# coil_driver.net
KiCad netlist of a schematic drawn in EAGLE
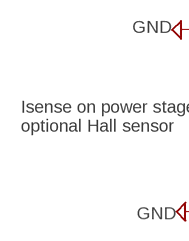
[diagram p0: schematic, sheet 1, part 1 of 2]
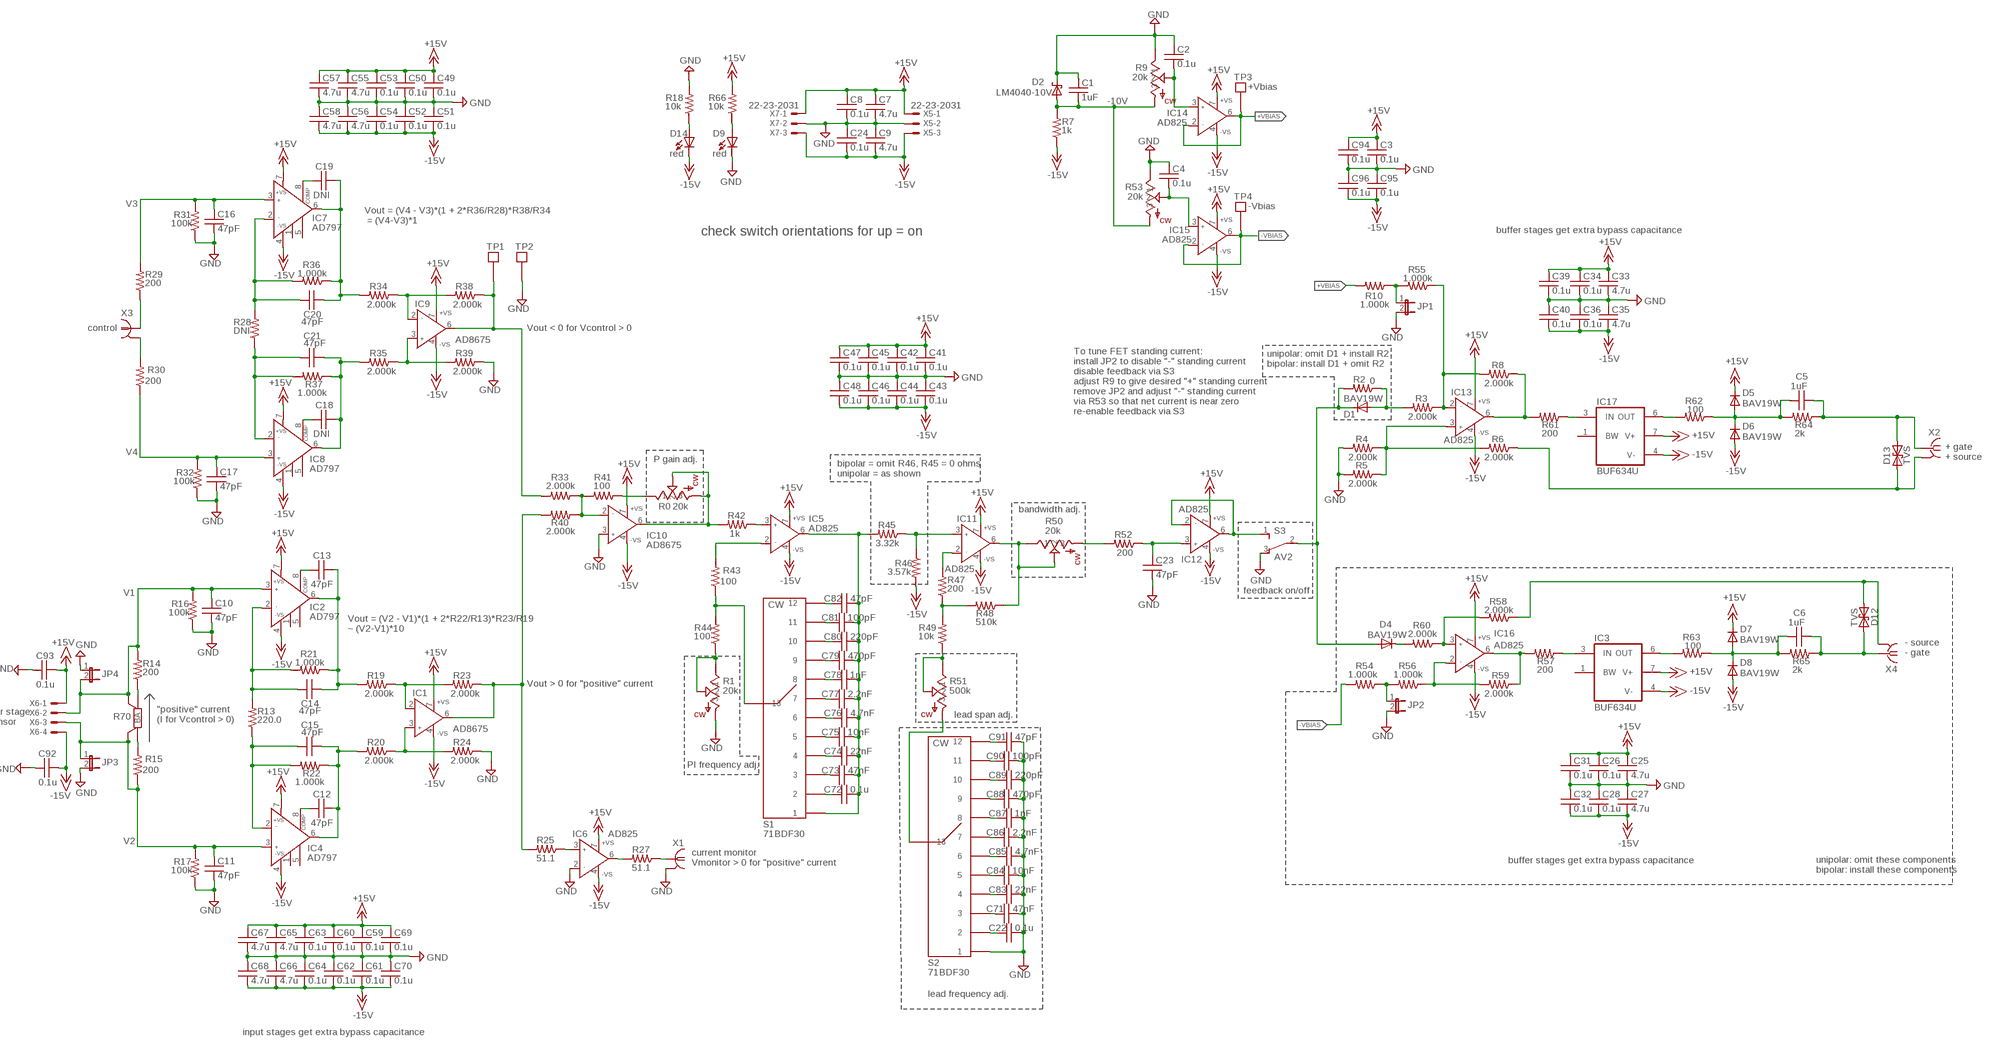
[diagram p1: schematic, sheet 1, part 2 of 2]

(export (version "E")
  (design (tool "Eeschema 10.0.6"))
  (components
    (comp (ref "C1")
      (value "1uF")
      (footprint "eagle-import:0603")
      (libsource (lib "eagle-import") (part "C0603"))
    )
    (comp (ref "C2")
      (value "0.1u")
      (footprint "eagle-import:0603")
      (libsource (lib "eagle-import") (part "C0603"))
    )
    (comp (ref "C3")
      (value "0.1u")
      (footprint "eagle-import:0603")
      (libsource (lib "eagle-import") (part "C0603"))
    )
    (comp (ref "C4")
      (value "0.1u")
      (footprint "eagle-import:0603")
      (libsource (lib "eagle-import") (part "C0603"))
    )
    (comp (ref "C5")
      (value "1uF")
      (footprint "eagle-import:0603")
      (libsource (lib "eagle-import") (part "C0603"))
    )
    (comp (ref "C6")
      (value "1uF")
      (footprint "eagle-import:0603")
      (libsource (lib "eagle-import") (part "C0603"))
    )
    (comp (ref "C7")
      (value "4.7u")
      (footprint "eagle-import:0603")
      (libsource (lib "eagle-import") (part "C0603"))
    )
    (comp (ref "C8")
      (value "0.1u")
      (footprint "eagle-import:0603")
      (libsource (lib "eagle-import") (part "C0603"))
    )
    (comp (ref "C9")
      (value "4.7u")
      (footprint "eagle-import:0603")
      (libsource (lib "eagle-import") (part "C0603"))
    )
    (comp (ref "C10")
      (value "47pF")
      (footprint "eagle-import:0603")
      (libsource (lib "eagle-import") (part "C0603"))
    )
    (comp (ref "C11")
      (value "47pF")
      (footprint "eagle-import:0603")
      (libsource (lib "eagle-import") (part "C0603"))
    )
    (comp (ref "C12")
      (value "47pF")
      (footprint "eagle-import:0603")
      (libsource (lib "eagle-import") (part "C0603"))
    )
    (comp (ref "C13")
      (value "47pF")
      (footprint "eagle-import:0603")
      (libsource (lib "eagle-import") (part "C0603"))
    )
    (comp (ref "C14")
      (value "47pF")
      (footprint "eagle-import:0603")
      (libsource (lib "eagle-import") (part "C0603"))
    )
    (comp (ref "C15")
      (value "47pF")
      (footprint "eagle-import:0603")
      (libsource (lib "eagle-import") (part "C0603"))
    )
    (comp (ref "C16")
      (value "47pF")
      (footprint "eagle-import:0603")
      (libsource (lib "eagle-import") (part "C0603"))
    )
    (comp (ref "C17")
      (value "47pF")
      (footprint "eagle-import:0603")
      (libsource (lib "eagle-import") (part "C0603"))
    )
    (comp (ref "C18")
      (value "DNI")
      (footprint "eagle-import:0603")
      (libsource (lib "eagle-import") (part "C0603"))
    )
    (comp (ref "C19")
      (value "DNI")
      (footprint "eagle-import:0603")
      (libsource (lib "eagle-import") (part "C0603"))
    )
    (comp (ref "C20")
      (value "47pF")
      (footprint "eagle-import:0603")
      (libsource (lib "eagle-import") (part "C0603"))
    )
    (comp (ref "C21")
      (value "47pF")
      (footprint "eagle-import:0603")
      (libsource (lib "eagle-import") (part "C0603"))
    )
    (comp (ref "C22")
      (value "0.1u")
      (footprint "eagle-import:0603")
      (libsource (lib "eagle-import") (part "C0603"))
    )
    (comp (ref "C23")
      (value "47pF")
      (footprint "eagle-import:0603")
      (libsource (lib "eagle-import") (part "C0603"))
    )
    (comp (ref "C24")
      (value "0.1u")
      (footprint "eagle-import:0603")
      (libsource (lib "eagle-import") (part "C0603"))
    )
    (comp (ref "C25")
      (value "4.7u")
      (footprint "eagle-import:0603")
      (libsource (lib "eagle-import") (part "C0603"))
    )
    (comp (ref "C26")
      (value "0.1u")
      (footprint "eagle-import:0603")
      (libsource (lib "eagle-import") (part "C0603"))
    )
    (comp (ref "C27")
      (value "4.7u")
      (footprint "eagle-import:0603")
      (libsource (lib "eagle-import") (part "C0603"))
    )
    (comp (ref "C28")
      (value "0.1u")
      (footprint "eagle-import:0603")
      (libsource (lib "eagle-import") (part "C0603"))
    )
    (comp (ref "C31")
      (value "0.1u")
      (footprint "eagle-import:0603")
      (libsource (lib "eagle-import") (part "C0603"))
    )
    (comp (ref "C32")
      (value "0.1u")
      (footprint "eagle-import:0603")
      (libsource (lib "eagle-import") (part "C0603"))
    )
    (comp (ref "C33")
      (value "4.7u")
      (footprint "eagle-import:0603")
      (libsource (lib "eagle-import") (part "C0603"))
    )
    (comp (ref "C34")
      (value "0.1u")
      (footprint "eagle-import:0603")
      (libsource (lib "eagle-import") (part "C0603"))
    )
    (comp (ref "C35")
      (value "4.7u")
      (footprint "eagle-import:0603")
      (libsource (lib "eagle-import") (part "C0603"))
    )
    (comp (ref "C36")
      (value "0.1u")
      (footprint "eagle-import:0603")
      (libsource (lib "eagle-import") (part "C0603"))
    )
    (comp (ref "C39")
      (value "0.1u")
      (footprint "eagle-import:0603")
      (libsource (lib "eagle-import") (part "C0603"))
    )
    (comp (ref "C40")
      (value "0.1u")
      (footprint "eagle-import:0603")
      (libsource (lib "eagle-import") (part "C0603"))
    )
    (comp (ref "C41")
      (value "0.1u")
      (footprint "eagle-import:0603")
      (libsource (lib "eagle-import") (part "C0603"))
    )
    (comp (ref "C42")
      (value "0.1u")
      (footprint "eagle-import:0603")
      (libsource (lib "eagle-import") (part "C0603"))
    )
    (comp (ref "C43")
      (value "0.1u")
      (footprint "eagle-import:0603")
      (libsource (lib "eagle-import") (part "C0603"))
    )
    (comp (ref "C44")
      (value "0.1u")
      (footprint "eagle-import:0603")
      (libsource (lib "eagle-import") (part "C0603"))
    )
    (comp (ref "C45")
      (value "0.1u")
      (footprint "eagle-import:0603")
      (libsource (lib "eagle-import") (part "C0603"))
    )
    (comp (ref "C46")
      (value "0.1u")
      (footprint "eagle-import:0603")
      (libsource (lib "eagle-import") (part "C0603"))
    )
    (comp (ref "C47")
      (value "0.1u")
      (footprint "eagle-import:0603")
      (libsource (lib "eagle-import") (part "C0603"))
    )
    (comp (ref "C48")
      (value "0.1u")
      (footprint "eagle-import:0603")
      (libsource (lib "eagle-import") (part "C0603"))
    )
    (comp (ref "C49")
      (value "0.1u")
      (footprint "eagle-import:0603")
      (libsource (lib "eagle-import") (part "C0603"))
    )
    (comp (ref "C50")
      (value "0.1u")
      (footprint "eagle-import:0603")
      (libsource (lib "eagle-import") (part "C0603"))
    )
    (comp (ref "C51")
      (value "0.1u")
      (footprint "eagle-import:0603")
      (libsource (lib "eagle-import") (part "C0603"))
    )
    (comp (ref "C52")
      (value "0.1u")
      (footprint "eagle-import:0603")
      (libsource (lib "eagle-import") (part "C0603"))
    )
    (comp (ref "C53")
      (value "0.1u")
      (footprint "eagle-import:0603")
      (libsource (lib "eagle-import") (part "C0603"))
    )
    (comp (ref "C54")
      (value "0.1u")
      (footprint "eagle-import:0603")
      (libsource (lib "eagle-import") (part "C0603"))
    )
    (comp (ref "C55")
      (value "4.7u")
      (footprint "eagle-import:0603")
      (libsource (lib "eagle-import") (part "C0603"))
    )
    (comp (ref "C56")
      (value "4.7u")
      (footprint "eagle-import:0603")
      (libsource (lib "eagle-import") (part "C0603"))
    )
    (comp (ref "C57")
      (value "4.7u")
      (footprint "eagle-import:0603")
      (libsource (lib "eagle-import") (part "C0603"))
    )
    (comp (ref "C58")
      (value "4.7u")
      (footprint "eagle-import:0603")
      (libsource (lib "eagle-import") (part "C0603"))
    )
    (comp (ref "C59")
      (value "0.1u")
      (footprint "eagle-import:0603")
      (libsource (lib "eagle-import") (part "C0603"))
    )
    (comp (ref "C60")
      (value "0.1u")
      (footprint "eagle-import:0603")
      (libsource (lib "eagle-import") (part "C0603"))
    )
    (comp (ref "C61")
      (value "0.1u")
      (footprint "eagle-import:0603")
      (libsource (lib "eagle-import") (part "C0603"))
    )
    (comp (ref "C62")
      (value "0.1u")
      (footprint "eagle-import:0603")
      (libsource (lib "eagle-import") (part "C0603"))
    )
    (comp (ref "C63")
      (value "0.1u")
      (footprint "eagle-import:0603")
      (libsource (lib "eagle-import") (part "C0603"))
    )
    (comp (ref "C64")
      (value "0.1u")
      (footprint "eagle-import:0603")
      (libsource (lib "eagle-import") (part "C0603"))
    )
    (comp (ref "C65")
      (value "4.7u")
      (footprint "eagle-import:0603")
      (libsource (lib "eagle-import") (part "C0603"))
    )
    (comp (ref "C66")
      (value "4.7u")
      (footprint "eagle-import:0603")
      (libsource (lib "eagle-import") (part "C0603"))
    )
    (comp (ref "C67")
      (value "4.7u")
      (footprint "eagle-import:0603")
      (libsource (lib "eagle-import") (part "C0603"))
    )
    (comp (ref "C68")
      (value "4.7u")
      (footprint "eagle-import:0603")
      (libsource (lib "eagle-import") (part "C0603"))
    )
    (comp (ref "C69")
      (value "0.1u")
      (footprint "eagle-import:0603")
      (libsource (lib "eagle-import") (part "C0603"))
    )
    (comp (ref "C70")
      (value "0.1u")
      (footprint "eagle-import:0603")
      (libsource (lib "eagle-import") (part "C0603"))
    )
    (comp (ref "C71")
      (value "47nF")
      (footprint "eagle-import:0603")
      (libsource (lib "eagle-import") (part "C0603"))
    )
    (comp (ref "C72")
      (value "0.1u")
      (footprint "eagle-import:0603")
      (libsource (lib "eagle-import") (part "C0603"))
    )
    (comp (ref "C73")
      (value "47nF")
      (footprint "eagle-import:0603")
      (libsource (lib "eagle-import") (part "C0603"))
    )
    (comp (ref "C74")
      (value "22nF")
      (footprint "eagle-import:0603")
      (libsource (lib "eagle-import") (part "C0603"))
    )
    (comp (ref "C75")
      (value "10nF")
      (footprint "eagle-import:0603")
      (libsource (lib "eagle-import") (part "C0603"))
    )
    (comp (ref "C76")
      (value "4.7nF")
      (footprint "eagle-import:0603")
      (libsource (lib "eagle-import") (part "C0603"))
    )
    (comp (ref "C77")
      (value "2.2nF")
      (footprint "eagle-import:0603")
      (libsource (lib "eagle-import") (part "C0603"))
    )
    (comp (ref "C78")
      (value "1nF")
      (footprint "eagle-import:0603")
      (libsource (lib "eagle-import") (part "C0603"))
    )
    (comp (ref "C79")
      (value "470pF")
      (footprint "eagle-import:0603")
      (libsource (lib "eagle-import") (part "C0603"))
    )
    (comp (ref "C80")
      (value "220pF")
      (footprint "eagle-import:0603")
      (libsource (lib "eagle-import") (part "C0603"))
    )
    (comp (ref "C81")
      (value "100pF")
      (footprint "eagle-import:0603")
      (libsource (lib "eagle-import") (part "C0603"))
    )
    (comp (ref "C82")
      (value "47pF")
      (footprint "eagle-import:0603")
      (libsource (lib "eagle-import") (part "C0603"))
    )
    (comp (ref "C83")
      (value "22nF")
      (footprint "eagle-import:0603")
      (libsource (lib "eagle-import") (part "C0603"))
    )
    (comp (ref "C84")
      (value "10nF")
      (footprint "eagle-import:0603")
      (libsource (lib "eagle-import") (part "C0603"))
    )
    (comp (ref "C85")
      (value "4.7nF")
      (footprint "eagle-import:0603")
      (libsource (lib "eagle-import") (part "C0603"))
    )
    (comp (ref "C86")
      (value "2.2nF")
      (footprint "eagle-import:0603")
      (libsource (lib "eagle-import") (part "C0603"))
    )
    (comp (ref "C87")
      (value "1nF")
      (footprint "eagle-import:0603")
      (libsource (lib "eagle-import") (part "C0603"))
    )
    (comp (ref "C88")
      (value "470pF")
      (footprint "eagle-import:0603")
      (libsource (lib "eagle-import") (part "C0603"))
    )
    (comp (ref "C89")
      (value "220pF")
      (footprint "eagle-import:0603")
      (libsource (lib "eagle-import") (part "C0603"))
    )
    (comp (ref "C90")
      (value "100pF")
      (footprint "eagle-import:0603")
      (libsource (lib "eagle-import") (part "C0603"))
    )
    (comp (ref "C91")
      (value "47pF")
      (footprint "eagle-import:0603")
      (libsource (lib "eagle-import") (part "C0603"))
    )
    (comp (ref "C92")
      (value "0.1u")
      (footprint "eagle-import:0603")
      (libsource (lib "eagle-import") (part "C0603"))
    )
    (comp (ref "C93")
      (value "0.1u")
      (footprint "eagle-import:0603")
      (libsource (lib "eagle-import") (part "C0603"))
    )
    (comp (ref "C94")
      (value "0.1u")
      (footprint "eagle-import:0603")
      (libsource (lib "eagle-import") (part "C0603"))
    )
    (comp (ref "C95")
      (value "0.1u")
      (footprint "eagle-import:0603")
      (libsource (lib "eagle-import") (part "C0603"))
    )
    (comp (ref "C96")
      (value "0.1u")
      (footprint "eagle-import:0603")
      (libsource (lib "eagle-import") (part "C0603"))
    )
    (comp (ref "D1")
      (value "BAV19W")
      (footprint "eagle-import:SOD123")
      (libsource (lib "eagle-import") (part "DIODE-SOD123"))
    )
    (comp (ref "D2")
      (value "LM4040-10V")
      (footprint "eagle-import:SOT23")
      (libsource (lib "eagle-import") (part "LM4040"))
    )
    (comp (ref "D4")
      (value "BAV19W")
      (footprint "eagle-import:SOD123")
      (libsource (lib "eagle-import") (part "DIODE-SOD123"))
    )
    (comp (ref "D5")
      (value "BAV19W")
      (footprint "eagle-import:SOD123")
      (libsource (lib "eagle-import") (part "DIODE-SOD123"))
    )
    (comp (ref "D6")
      (value "BAV19W")
      (footprint "eagle-import:SOD123")
      (libsource (lib "eagle-import") (part "DIODE-SOD123"))
    )
    (comp (ref "D7")
      (value "BAV19W")
      (footprint "eagle-import:SOD123")
      (libsource (lib "eagle-import") (part "DIODE-SOD123"))
    )
    (comp (ref "D8")
      (value "BAV19W")
      (footprint "eagle-import:SOD123")
      (libsource (lib "eagle-import") (part "DIODE-SOD123"))
    )
    (comp (ref "D9")
      (value "red")
      (footprint "eagle-import:LED0603")
      (libsource (lib "eagle-import") (part "LED0603"))
    )
    (comp (ref "D12")
      (value "TVS")
      (footprint "eagle-import:SMA-DIODE")
      (libsource (lib "eagle-import") (part "TVS"))
    )
    (comp (ref "D13")
      (value "TVS")
      (footprint "eagle-import:SMA-DIODE")
      (libsource (lib "eagle-import") (part "TVS"))
    )
    (comp (ref "D14")
      (value "red")
      (footprint "eagle-import:LED0603")
      (libsource (lib "eagle-import") (part "LED0603"))
    )
    (comp (ref "IC1")
      (value "AD8675")
      (footprint "eagle-import:SO8")
      (fields (field (name "MF") "ALTERA CORPORATION") (field (name "MPN") "AD825ARZ"))
      (libsource (lib "eagle-import") (part "AD825_BR"))
    )
    (comp (ref "IC2")
      (value "AD797")
      (footprint "eagle-import:SO8")
      (fields (field (name "MF") "ALTERA CORPORATION") (field (name "MPN") "AD797ARZ"))
      (libsource (lib "eagle-import") (part "AD797_AR"))
    )
    (comp (ref "IC3")
      (value "BUF634U")
      (footprint "eagle-import:SO08")
      (fields (field (name "MF") "TEXAS INSTRUMENTS"))
      (libsource (lib "eagle-import") (part "BUF634U"))
    )
    (comp (ref "IC4")
      (value "AD797")
      (footprint "eagle-import:SO8")
      (fields (field (name "MF") "ALTERA CORPORATION") (field (name "MPN") "AD797ARZ"))
      (libsource (lib "eagle-import") (part "AD797_BR"))
    )
    (comp (ref "IC5")
      (value "AD825")
      (footprint "eagle-import:SO08")
      (libsource (lib "eagle-import") (part "AD825_A"))
    )
    (comp (ref "IC6")
      (value "AD825")
      (footprint "eagle-import:SO08")
      (libsource (lib "eagle-import") (part "AD825_A"))
    )
    (comp (ref "IC7")
      (value "AD797")
      (footprint "eagle-import:SO8")
      (fields (field (name "MF") "ALTERA CORPORATION") (field (name "MPN") "AD797ARZ"))
      (libsource (lib "eagle-import") (part "AD797_AR"))
    )
    (comp (ref "IC8")
      (value "AD797")
      (footprint "eagle-import:SO8")
      (fields (field (name "MF") "ALTERA CORPORATION") (field (name "MPN") "AD797ARZ"))
      (libsource (lib "eagle-import") (part "AD797_BR"))
    )
    (comp (ref "IC9")
      (value "AD8675")
      (footprint "eagle-import:SO8")
      (fields (field (name "MF") "ALTERA CORPORATION") (field (name "MPN") "AD825ARZ"))
      (libsource (lib "eagle-import") (part "AD825_BR"))
    )
    (comp (ref "IC10")
      (value "AD8675")
      (footprint "eagle-import:SO8")
      (fields (field (name "MF") "ALTERA CORPORATION") (field (name "MPN") "AD825ARZ"))
      (libsource (lib "eagle-import") (part "AD825_BR"))
    )
    (comp (ref "IC11")
      (value "AD825")
      (footprint "eagle-import:SO08")
      (libsource (lib "eagle-import") (part "AD825_A"))
    )
    (comp (ref "IC12")
      (value "AD825")
      (footprint "eagle-import:SO8")
      (fields (field (name "MF") "ALTERA CORPORATION") (field (name "MPN") "AD825ARZ"))
      (libsource (lib "eagle-import") (part "AD825_BR"))
    )
    (comp (ref "IC13")
      (value "AD825")
      (footprint "eagle-import:SO8")
      (fields (field (name "MF") "ALTERA CORPORATION") (field (name "MPN") "AD825ARZ"))
      (libsource (lib "eagle-import") (part "AD825_BR"))
    )
    (comp (ref "IC14")
      (value "AD825")
      (footprint "eagle-import:SO08")
      (libsource (lib "eagle-import") (part "AD825_A"))
    )
    (comp (ref "IC15")
      (value "AD825")
      (footprint "eagle-import:SO08")
      (libsource (lib "eagle-import") (part "AD825_A"))
    )
    (comp (ref "IC16")
      (value "AD825")
      (footprint "eagle-import:SO08")
      (libsource (lib "eagle-import") (part "AD825_A"))
    )
    (comp (ref "IC17")
      (value "BUF634U")
      (footprint "eagle-import:SO08")
      (fields (field (name "MF") "TEXAS INSTRUMENTS"))
      (libsource (lib "eagle-import") (part "BUF634U"))
    )
    (comp (ref "JP1")
      (value "JP1E")
      (footprint "eagle-import:JP1")
      (libsource (lib "eagle-import") (part "JP1E"))
    )
    (comp (ref "JP2")
      (value "JP1E")
      (footprint "eagle-import:JP1")
      (libsource (lib "eagle-import") (part "JP1E"))
    )
    (comp (ref "JP3")
      (value "JP1E")
      (footprint "eagle-import:JP1")
      (libsource (lib "eagle-import") (part "JP1E"))
    )
    (comp (ref "JP4")
      (value "JP1E")
      (footprint "eagle-import:JP1")
      (libsource (lib "eagle-import") (part "JP1E"))
    )
    (comp (ref "R0")
      (value "20k")
      (footprint "eagle-import:3590")
      (libsource (lib "eagle-import") (part "POT"))
    )
    (comp (ref "R1")
      (value "20k")
      (footprint "eagle-import:SP19L")
      (libsource (lib "eagle-import") (part "TRIM_US-B90P"))
    )
    (comp (ref "R2")
      (value "0")
      (footprint "eagle-import:0603")
      (libsource (lib "eagle-import") (part "R0603"))
    )
    (comp (ref "R3")
      (value "2.000k")
      (footprint "eagle-import:0603")
      (libsource (lib "eagle-import") (part "R0603"))
    )
    (comp (ref "R4")
      (value "2.000k")
      (footprint "eagle-import:0603")
      (libsource (lib "eagle-import") (part "R0603"))
    )
    (comp (ref "R5")
      (value "2.000k")
      (footprint "eagle-import:0603")
      (libsource (lib "eagle-import") (part "R0603"))
    )
    (comp (ref "R6")
      (value "2.000k")
      (footprint "eagle-import:0603")
      (libsource (lib "eagle-import") (part "R0603"))
    )
    (comp (ref "R7")
      (value "1k")
      (footprint "eagle-import:0603")
      (libsource (lib "eagle-import") (part "R0603"))
    )
    (comp (ref "R8")
      (value "2.000k")
      (footprint "eagle-import:0603")
      (libsource (lib "eagle-import") (part "R0603"))
    )
    (comp (ref "R9")
      (value "20k")
      (footprint "eagle-import:SP19L")
      (libsource (lib "eagle-import") (part "TRIM_US-B90P"))
    )
    (comp (ref "R10")
      (value "1.000k")
      (footprint "eagle-import:0603")
      (libsource (lib "eagle-import") (part "R0603"))
    )
    (comp (ref "R13")
      (value "220.0")
      (footprint "eagle-import:0603")
      (libsource (lib "eagle-import") (part "R0603"))
    )
    (comp (ref "R14")
      (value "200")
      (footprint "eagle-import:0603")
      (libsource (lib "eagle-import") (part "R0603"))
    )
    (comp (ref "R15")
      (value "200")
      (footprint "eagle-import:0603")
      (libsource (lib "eagle-import") (part "R0603"))
    )
    (comp (ref "R16")
      (value "100k")
      (footprint "eagle-import:0603")
      (libsource (lib "eagle-import") (part "R0603"))
    )
    (comp (ref "R17")
      (value "100k")
      (footprint "eagle-import:0603")
      (libsource (lib "eagle-import") (part "R0603"))
    )
    (comp (ref "R18")
      (value "10k")
      (footprint "eagle-import:0603")
      (libsource (lib "eagle-import") (part "R0603"))
    )
    (comp (ref "R19")
      (value "2.000k")
      (footprint "eagle-import:0603")
      (libsource (lib "eagle-import") (part "R0603"))
    )
    (comp (ref "R20")
      (value "2.000k")
      (footprint "eagle-import:0603")
      (libsource (lib "eagle-import") (part "R0603"))
    )
    (comp (ref "R21")
      (value "1.000k")
      (footprint "eagle-import:0603")
      (libsource (lib "eagle-import") (part "R0603"))
    )
    (comp (ref "R22")
      (value "1.000k")
      (footprint "eagle-import:0603")
      (libsource (lib "eagle-import") (part "R0603"))
    )
    (comp (ref "R23")
      (value "2.000k")
      (footprint "eagle-import:0603")
      (libsource (lib "eagle-import") (part "R0603"))
    )
    (comp (ref "R24")
      (value "2.000k")
      (footprint "eagle-import:0603")
      (libsource (lib "eagle-import") (part "R0603"))
    )
    (comp (ref "R25")
      (value "51.1")
      (footprint "eagle-import:0603")
      (libsource (lib "eagle-import") (part "R0603"))
    )
    (comp (ref "R27")
      (value "51.1")
      (footprint "eagle-import:0603")
      (libsource (lib "eagle-import") (part "R0603"))
    )
    (comp (ref "R28")
      (value "DNI")
      (footprint "eagle-import:0603")
      (libsource (lib "eagle-import") (part "R0603"))
    )
    (comp (ref "R29")
      (value "200")
      (footprint "eagle-import:0603")
      (libsource (lib "eagle-import") (part "R0603"))
    )
    (comp (ref "R30")
      (value "200")
      (footprint "eagle-import:0603")
      (libsource (lib "eagle-import") (part "R0603"))
    )
    (comp (ref "R31")
      (value "100k")
      (footprint "eagle-import:0603")
      (libsource (lib "eagle-import") (part "R0603"))
    )
    (comp (ref "R32")
      (value "100k")
      (footprint "eagle-import:0603")
      (libsource (lib "eagle-import") (part "R0603"))
    )
    (comp (ref "R33")
      (value "2.000k")
      (footprint "eagle-import:0603")
      (libsource (lib "eagle-import") (part "R0603"))
    )
    (comp (ref "R34")
      (value "2.000k")
      (footprint "eagle-import:0603")
      (libsource (lib "eagle-import") (part "R0603"))
    )
    (comp (ref "R35")
      (value "2.000k")
      (footprint "eagle-import:0603")
      (libsource (lib "eagle-import") (part "R0603"))
    )
    (comp (ref "R36")
      (value "1.000k")
      (footprint "eagle-import:0603")
      (libsource (lib "eagle-import") (part "R0603"))
    )
    (comp (ref "R37")
      (value "1.000k")
      (footprint "eagle-import:0603")
      (libsource (lib "eagle-import") (part "R0603"))
    )
    (comp (ref "R38")
      (value "2.000k")
      (footprint "eagle-import:0603")
      (libsource (lib "eagle-import") (part "R0603"))
    )
    (comp (ref "R39")
      (value "2.000k")
      (footprint "eagle-import:0603")
      (libsource (lib "eagle-import") (part "R0603"))
    )
    (comp (ref "R40")
      (value "2.000k")
      (footprint "eagle-import:0603")
      (libsource (lib "eagle-import") (part "R0603"))
    )
    (comp (ref "R41")
      (value "100")
      (footprint "eagle-import:0603")
      (libsource (lib "eagle-import") (part "R0603"))
    )
    (comp (ref "R42")
      (value "1k")
      (footprint "eagle-import:0603")
      (libsource (lib "eagle-import") (part "R0603"))
    )
    (comp (ref "R43")
      (value "100")
      (footprint "eagle-import:0603")
      (libsource (lib "eagle-import") (part "R0603"))
    )
    (comp (ref "R44")
      (value "100")
      (footprint "eagle-import:0603")
      (libsource (lib "eagle-import") (part "R0603"))
    )
    (comp (ref "R45")
      (value "3.32k")
      (footprint "eagle-import:0603")
      (libsource (lib "eagle-import") (part "R0603"))
    )
    (comp (ref "R46")
      (value "3.57k")
      (footprint "eagle-import:0603")
      (libsource (lib "eagle-import") (part "R0603"))
    )
    (comp (ref "R47")
      (value "200")
      (footprint "eagle-import:0603")
      (libsource (lib "eagle-import") (part "R0603"))
    )
    (comp (ref "R48")
      (value "510k")
      (footprint "eagle-import:0603")
      (libsource (lib "eagle-import") (part "R0603"))
    )
    (comp (ref "R49")
      (value "10k")
      (footprint "eagle-import:0603")
      (libsource (lib "eagle-import") (part "R0603"))
    )
    (comp (ref "R50")
      (value "20k")
      (footprint "eagle-import:SP19L")
      (libsource (lib "eagle-import") (part "TRIM_US-B90P"))
    )
    (comp (ref "R51")
      (value "500k")
      (footprint "eagle-import:SP19L")
      (libsource (lib "eagle-import") (part "TRIM_US-B90P"))
    )
    (comp (ref "R52")
      (value "200")
      (footprint "eagle-import:0603")
      (libsource (lib "eagle-import") (part "R0603"))
    )
    (comp (ref "R53")
      (value "20k")
      (footprint "eagle-import:SP19L")
      (libsource (lib "eagle-import") (part "TRIM_US-B90P"))
    )
    (comp (ref "R54")
      (value "1.000k")
      (footprint "eagle-import:0603")
      (libsource (lib "eagle-import") (part "R0603"))
    )
    (comp (ref "R55")
      (value "1.000k")
      (footprint "eagle-import:0603")
      (libsource (lib "eagle-import") (part "R0603"))
    )
    (comp (ref "R56")
      (value "1.000k")
      (footprint "eagle-import:0603")
      (libsource (lib "eagle-import") (part "R0603"))
    )
    (comp (ref "R57")
      (value "200")
      (footprint "eagle-import:0603")
      (libsource (lib "eagle-import") (part "R0603"))
    )
    (comp (ref "R58")
      (value "2.000k")
      (footprint "eagle-import:0603")
      (libsource (lib "eagle-import") (part "R0603"))
    )
    (comp (ref "R59")
      (value "2.000k")
      (footprint "eagle-import:0603")
      (libsource (lib "eagle-import") (part "R0603"))
    )
    (comp (ref "R60")
      (value "2.000k")
      (footprint "eagle-import:0603")
      (libsource (lib "eagle-import") (part "R0603"))
    )
    (comp (ref "R61")
      (value "200")
      (footprint "eagle-import:0603")
      (libsource (lib "eagle-import") (part "R0603"))
    )
    (comp (ref "R62")
      (value "100")
      (footprint "eagle-import:0603")
      (libsource (lib "eagle-import") (part "R0603"))
    )
    (comp (ref "R63")
      (value "100")
      (footprint "eagle-import:0603")
      (libsource (lib "eagle-import") (part "R0603"))
    )
    (comp (ref "R64")
      (value "2k")
      (footprint "eagle-import:0603")
      (libsource (lib "eagle-import") (part "R0603"))
    )
    (comp (ref "R65")
      (value "2k")
      (footprint "eagle-import:0603")
      (libsource (lib "eagle-import") (part "R0603"))
    )
    (comp (ref "R66")
      (value "10k")
      (footprint "eagle-import:0603")
      (libsource (lib "eagle-import") (part "R0603"))
    )
    (comp (ref "R70")
      (value "RSENSE")
      (footprint "eagle-import:22-23-2041")
      (libsource (lib "eagle-import") (part "RSENSE"))
    )
    (comp (ref "S1")
      (value "71BDF30")
      (footprint "eagle-import:71BDF")
      (libsource (lib "eagle-import") (part "71BDF30"))
    )
    (comp (ref "S2")
      (value "71BDF30")
      (footprint "eagle-import:71BDF")
      (libsource (lib "eagle-import") (part "71BDF30"))
    )
    (comp (ref "S3")
      (value "AV2")
      (footprint "eagle-import:SPDT-AV2")
      (libsource (lib "eagle-import") (part "SPDT"))
    )
    (comp (ref "TP1")
      (value "TESTPOINT")
      (footprint "eagle-import:TESTPOINT")
      (libsource (lib "eagle-import") (part "TESTPOINT"))
    )
    (comp (ref "TP2")
      (value "TESTPOINT")
      (footprint "eagle-import:TESTPOINT")
      (libsource (lib "eagle-import") (part "TESTPOINT"))
    )
    (comp (ref "TP3")
      (value "TESTPOINT")
      (footprint "eagle-import:TESTPOINT")
      (libsource (lib "eagle-import") (part "TESTPOINT"))
    )
    (comp (ref "TP4")
      (value "TESTPOINT")
      (footprint "eagle-import:TESTPOINT")
      (libsource (lib "eagle-import") (part "TESTPOINT"))
    )
    (comp (ref "X1")
      (value "1-227161-0")
      (footprint "eagle-import:AMP_227161")
      (fields (field (name "MF") "TYCO ELECTRONICS") (field (name "MPN") "1-227161"))
      (libsource (lib "eagle-import") (part "?2271611--0"))
    )
    (comp (ref "X2")
      (value "BU-SMA-H")
      (footprint "eagle-import:BU-SMA-H")
      (libsource (lib "eagle-import") (part "BU-SMA-H"))
    )
    (comp (ref "X3")
      (value "1-227161-0")
      (footprint "eagle-import:AMP_227161")
      (fields (field (name "MF") "TYCO ELECTRONICS") (field (name "MPN") "1-227161"))
      (libsource (lib "eagle-import") (part "?2271611--0"))
    )
    (comp (ref "X4")
      (value "BU-SMA-H")
      (footprint "eagle-import:BU-SMA-H")
      (libsource (lib "eagle-import") (part "BU-SMA-H"))
    )
    (comp (ref "X5")
      (value "22-23-2031")
      (footprint "eagle-import:22-23-2031")
      (fields (field (name "MF") "MOLEX"))
      (libsource (lib "eagle-import") (part "22-23-2031"))
    )
    (comp (ref "X6")
      (value "22-23-2041")
      (footprint "eagle-import:22-23-2041")
      (fields (field (name "MF") "MOLEX"))
      (libsource (lib "eagle-import") (part "22-23-2041"))
    )
    (comp (ref "X7")
      (value "22-23-2031")
      (footprint "eagle-import:22-23-2031")
      (fields (field (name "MF") "MOLEX"))
      (libsource (lib "eagle-import") (part "22-23-2031"))
    )
  )
  (nets
    (net (code "1") (name "+15V") (class "Default")
      (node (ref "C25") (pin "1") (pinfunction "1_1") (pintype "passive"))
      (node (ref "C26") (pin "1") (pinfunction "1_1") (pintype "passive"))
      (node (ref "C3") (pin "1") (pinfunction "1_1") (pintype "passive"))
      (node (ref "C31") (pin "1") (pinfunction "1_1") (pintype "passive"))
      (node (ref "C33") (pin "1") (pinfunction "1_1") (pintype "passive"))
      (node (ref "C34") (pin "1") (pinfunction "1_1") (pintype "passive"))
      (node (ref "C39") (pin "1") (pinfunction "1_1") (pintype "passive"))
      (node (ref "C41") (pin "1") (pinfunction "1_1") (pintype "passive"))
      (node (ref "C42") (pin "1") (pinfunction "1_1") (pintype "passive"))
      (node (ref "C45") (pin "1") (pinfunction "1_1") (pintype "passive"))
      (node (ref "C47") (pin "1") (pinfunction "1_1") (pintype "passive"))
      (node (ref "C49") (pin "1") (pinfunction "1_1") (pintype "passive"))
      (node (ref "C50") (pin "1") (pinfunction "1_1") (pintype "passive"))
      (node (ref "C53") (pin "1") (pinfunction "1_1") (pintype "passive"))
      (node (ref "C55") (pin "1") (pinfunction "1_1") (pintype "passive"))
      (node (ref "C57") (pin "1") (pinfunction "1_1") (pintype "passive"))
      (node (ref "C59") (pin "1") (pinfunction "1_1") (pintype "passive"))
      (node (ref "C60") (pin "1") (pinfunction "1_1") (pintype "passive"))
      (node (ref "C63") (pin "1") (pinfunction "1_1") (pintype "passive"))
      (node (ref "C65") (pin "1") (pinfunction "1_1") (pintype "passive"))
      (node (ref "C67") (pin "1") (pinfunction "1_1") (pintype "passive"))
      (node (ref "C69") (pin "1") (pinfunction "1_1") (pintype "passive"))
      (node (ref "C7") (pin "1") (pinfunction "1_1") (pintype "passive"))
      (node (ref "C8") (pin "1") (pinfunction "1_1") (pintype "passive"))
      (node (ref "C93") (pin "2") (pinfunction "2_2") (pintype "passive"))
      (node (ref "C94") (pin "1") (pinfunction "1_1") (pintype "passive"))
      (node (ref "D5") (pin "C") (pinfunction "C_C") (pintype "passive"))
      (node (ref "D7") (pin "C") (pinfunction "C_C") (pintype "passive"))
      (node (ref "IC1") (pin "7") (pinfunction "+VS_7") (pintype "input"))
      (node (ref "IC10") (pin "7") (pinfunction "+VS_7") (pintype "input"))
      (node (ref "IC11") (pin "7") (pinfunction "+VS_7") (pintype "input"))
      (node (ref "IC12") (pin "7") (pinfunction "+VS_7") (pintype "input"))
      (node (ref "IC13") (pin "7") (pinfunction "+VS_7") (pintype "input"))
      (node (ref "IC14") (pin "7") (pinfunction "+VS_7") (pintype "input"))
      (node (ref "IC15") (pin "7") (pinfunction "+VS_7") (pintype "input"))
      (node (ref "IC16") (pin "7") (pinfunction "+VS_7") (pintype "input"))
      (node (ref "IC17") (pin "7") (pinfunction "V+_7") (pintype "power_in"))
      (node (ref "IC2") (pin "7") (pinfunction "+VS_7") (pintype "input"))
      (node (ref "IC3") (pin "7") (pinfunction "V+_7") (pintype "power_in"))
      (node (ref "IC4") (pin "7") (pinfunction "+VS_7") (pintype "input"))
      (node (ref "IC5") (pin "7") (pinfunction "+VS_7") (pintype "input"))
      (node (ref "IC6") (pin "7") (pinfunction "+VS_7") (pintype "input"))
      (node (ref "IC7") (pin "7") (pinfunction "+VS_7") (pintype "input"))
      (node (ref "IC8") (pin "7") (pinfunction "+VS_7") (pintype "input"))
      (node (ref "IC9") (pin "7") (pinfunction "+VS_7") (pintype "input"))
      (node (ref "R66") (pin "2") (pinfunction "2_2") (pintype "passive"))
      (node (ref "X5") (pin "1") (pinfunction "S_1") (pintype "passive"))
      (node (ref "X6") (pin "1") (pinfunction "S_1") (pintype "passive"))
      (node (ref "X7") (pin "1") (pinfunction "S_1") (pintype "passive"))
    )
    (net (code "2") (name "+VBIAS") (class "Default")
      (node (ref "IC14") (pin "2") (pinfunction "IN-_2") (pintype "input"))
      (node (ref "IC14") (pin "6") (pinfunction "OUT_6") (pintype "output"))
      (node (ref "R10") (pin "2") (pinfunction "2_2") (pintype "passive"))
      (node (ref "TP3") (pin "P$1") (pinfunction "P$1_P$1") (pintype "bidirectional"))
    )
    (net (code "3") (name "-15V") (class "Default")
      (node (ref "C24") (pin "2") (pinfunction "2_2") (pintype "passive"))
      (node (ref "C27") (pin "2") (pinfunction "2_2") (pintype "passive"))
      (node (ref "C28") (pin "2") (pinfunction "2_2") (pintype "passive"))
      (node (ref "C32") (pin "2") (pinfunction "2_2") (pintype "passive"))
      (node (ref "C35") (pin "2") (pinfunction "2_2") (pintype "passive"))
      (node (ref "C36") (pin "2") (pinfunction "2_2") (pintype "passive"))
      (node (ref "C40") (pin "2") (pinfunction "2_2") (pintype "passive"))
      (node (ref "C43") (pin "2") (pinfunction "2_2") (pintype "passive"))
      (node (ref "C44") (pin "2") (pinfunction "2_2") (pintype "passive"))
      (node (ref "C46") (pin "2") (pinfunction "2_2") (pintype "passive"))
      (node (ref "C48") (pin "2") (pinfunction "2_2") (pintype "passive"))
      (node (ref "C51") (pin "2") (pinfunction "2_2") (pintype "passive"))
      (node (ref "C52") (pin "2") (pinfunction "2_2") (pintype "passive"))
      (node (ref "C54") (pin "2") (pinfunction "2_2") (pintype "passive"))
      (node (ref "C56") (pin "2") (pinfunction "2_2") (pintype "passive"))
      (node (ref "C58") (pin "2") (pinfunction "2_2") (pintype "passive"))
      (node (ref "C61") (pin "2") (pinfunction "2_2") (pintype "passive"))
      (node (ref "C62") (pin "2") (pinfunction "2_2") (pintype "passive"))
      (node (ref "C64") (pin "2") (pinfunction "2_2") (pintype "passive"))
      (node (ref "C66") (pin "2") (pinfunction "2_2") (pintype "passive"))
      (node (ref "C68") (pin "2") (pinfunction "2_2") (pintype "passive"))
      (node (ref "C70") (pin "2") (pinfunction "2_2") (pintype "passive"))
      (node (ref "C9") (pin "2") (pinfunction "2_2") (pintype "passive"))
      (node (ref "C92") (pin "2") (pinfunction "2_2") (pintype "passive"))
      (node (ref "C95") (pin "2") (pinfunction "2_2") (pintype "passive"))
      (node (ref "C96") (pin "2") (pinfunction "2_2") (pintype "passive"))
      (node (ref "D14") (pin "C") (pinfunction "C_C") (pintype "passive"))
      (node (ref "D6") (pin "A") (pinfunction "A_A") (pintype "passive"))
      (node (ref "D8") (pin "A") (pinfunction "A_A") (pintype "passive"))
      (node (ref "IC1") (pin "4") (pinfunction "-VS_4") (pintype "input"))
      (node (ref "IC10") (pin "4") (pinfunction "-VS_4") (pintype "input"))
      (node (ref "IC11") (pin "4") (pinfunction "-VS_4") (pintype "input"))
      (node (ref "IC12") (pin "4") (pinfunction "-VS_4") (pintype "input"))
      (node (ref "IC13") (pin "4") (pinfunction "-VS_4") (pintype "input"))
      (node (ref "IC14") (pin "4") (pinfunction "-VS_4") (pintype "input"))
      (node (ref "IC15") (pin "4") (pinfunction "-VS_4") (pintype "input"))
      (node (ref "IC16") (pin "4") (pinfunction "-VS_4") (pintype "input"))
      (node (ref "IC17") (pin "4") (pinfunction "V-_4") (pintype "power_in"))
      (node (ref "IC2") (pin "4") (pinfunction "-VS_4") (pintype "input"))
      (node (ref "IC3") (pin "4") (pinfunction "V-_4") (pintype "power_in"))
      (node (ref "IC4") (pin "4") (pinfunction "-VS_4") (pintype "input"))
      (node (ref "IC5") (pin "4") (pinfunction "-VS_4") (pintype "input"))
      (node (ref "IC6") (pin "4") (pinfunction "-VS_4") (pintype "input"))
      (node (ref "IC7") (pin "4") (pinfunction "-VS_4") (pintype "input"))
      (node (ref "IC8") (pin "4") (pinfunction "-VS_4") (pintype "input"))
      (node (ref "IC9") (pin "4") (pinfunction "-VS_4") (pintype "input"))
      (node (ref "R46") (pin "2") (pinfunction "2_2") (pintype "passive"))
      (node (ref "R7") (pin "1") (pinfunction "1_1") (pintype "passive"))
      (node (ref "X5") (pin "3") (pinfunction "S_3") (pintype "passive"))
      (node (ref "X6") (pin "4") (pinfunction "S_4") (pintype "passive"))
      (node (ref "X7") (pin "3") (pinfunction "S_3") (pintype "passive"))
    )
    (net (code "4") (name "-VBIAS") (class "Default")
      (node (ref "IC15") (pin "2") (pinfunction "IN-_2") (pintype "input"))
      (node (ref "IC15") (pin "6") (pinfunction "OUT_6") (pintype "output"))
      (node (ref "R54") (pin "2") (pinfunction "2_2") (pintype "passive"))
      (node (ref "TP4") (pin "P$1") (pinfunction "P$1_P$1") (pintype "bidirectional"))
    )
    (net (code "5") (name "GND") (class "Default")
      (node (ref "C1") (pin "1") (pinfunction "1_1") (pintype "passive"))
      (node (ref "C10") (pin "2") (pinfunction "2_2") (pintype "passive"))
      (node (ref "C11") (pin "2") (pinfunction "2_2") (pintype "passive"))
      (node (ref "C16") (pin "2") (pinfunction "2_2") (pintype "passive"))
      (node (ref "C17") (pin "2") (pinfunction "2_2") (pintype "passive"))
      (node (ref "C2") (pin "1") (pinfunction "1_1") (pintype "passive"))
      (node (ref "C22") (pin "2") (pinfunction "2_2") (pintype "passive"))
      (node (ref "C23") (pin "2") (pinfunction "2_2") (pintype "passive"))
      (node (ref "C24") (pin "1") (pinfunction "1_1") (pintype "passive"))
      (node (ref "C25") (pin "2") (pinfunction "2_2") (pintype "passive"))
      (node (ref "C26") (pin "2") (pinfunction "2_2") (pintype "passive"))
      (node (ref "C27") (pin "1") (pinfunction "1_1") (pintype "passive"))
      (node (ref "C28") (pin "1") (pinfunction "1_1") (pintype "passive"))
      (node (ref "C3") (pin "2") (pinfunction "2_2") (pintype "passive"))
      (node (ref "C31") (pin "2") (pinfunction "2_2") (pintype "passive"))
      (node (ref "C32") (pin "1") (pinfunction "1_1") (pintype "passive"))
      (node (ref "C33") (pin "2") (pinfunction "2_2") (pintype "passive"))
      (node (ref "C34") (pin "2") (pinfunction "2_2") (pintype "passive"))
      (node (ref "C35") (pin "1") (pinfunction "1_1") (pintype "passive"))
      (node (ref "C36") (pin "1") (pinfunction "1_1") (pintype "passive"))
      (node (ref "C39") (pin "2") (pinfunction "2_2") (pintype "passive"))
      (node (ref "C4") (pin "1") (pinfunction "1_1") (pintype "passive"))
      (node (ref "C40") (pin "1") (pinfunction "1_1") (pintype "passive"))
      (node (ref "C41") (pin "2") (pinfunction "2_2") (pintype "passive"))
      (node (ref "C42") (pin "2") (pinfunction "2_2") (pintype "passive"))
      (node (ref "C43") (pin "1") (pinfunction "1_1") (pintype "passive"))
      (node (ref "C44") (pin "1") (pinfunction "1_1") (pintype "passive"))
      (node (ref "C45") (pin "2") (pinfunction "2_2") (pintype "passive"))
      (node (ref "C46") (pin "1") (pinfunction "1_1") (pintype "passive"))
      (node (ref "C47") (pin "2") (pinfunction "2_2") (pintype "passive"))
      (node (ref "C48") (pin "1") (pinfunction "1_1") (pintype "passive"))
      (node (ref "C49") (pin "2") (pinfunction "2_2") (pintype "passive"))
      (node (ref "C50") (pin "2") (pinfunction "2_2") (pintype "passive"))
      (node (ref "C51") (pin "1") (pinfunction "1_1") (pintype "passive"))
      (node (ref "C52") (pin "1") (pinfunction "1_1") (pintype "passive"))
      (node (ref "C53") (pin "2") (pinfunction "2_2") (pintype "passive"))
      (node (ref "C54") (pin "1") (pinfunction "1_1") (pintype "passive"))
      (node (ref "C55") (pin "2") (pinfunction "2_2") (pintype "passive"))
      (node (ref "C56") (pin "1") (pinfunction "1_1") (pintype "passive"))
      (node (ref "C57") (pin "2") (pinfunction "2_2") (pintype "passive"))
      (node (ref "C58") (pin "1") (pinfunction "1_1") (pintype "passive"))
      (node (ref "C59") (pin "2") (pinfunction "2_2") (pintype "passive"))
      (node (ref "C60") (pin "2") (pinfunction "2_2") (pintype "passive"))
      (node (ref "C61") (pin "1") (pinfunction "1_1") (pintype "passive"))
      (node (ref "C62") (pin "1") (pinfunction "1_1") (pintype "passive"))
      (node (ref "C63") (pin "2") (pinfunction "2_2") (pintype "passive"))
      (node (ref "C64") (pin "1") (pinfunction "1_1") (pintype "passive"))
      (node (ref "C65") (pin "2") (pinfunction "2_2") (pintype "passive"))
      (node (ref "C66") (pin "1") (pinfunction "1_1") (pintype "passive"))
      (node (ref "C67") (pin "2") (pinfunction "2_2") (pintype "passive"))
      (node (ref "C68") (pin "1") (pinfunction "1_1") (pintype "passive"))
      (node (ref "C69") (pin "2") (pinfunction "2_2") (pintype "passive"))
      (node (ref "C7") (pin "2") (pinfunction "2_2") (pintype "passive"))
      (node (ref "C70") (pin "1") (pinfunction "1_1") (pintype "passive"))
      (node (ref "C71") (pin "2") (pinfunction "2_2") (pintype "passive"))
      (node (ref "C8") (pin "2") (pinfunction "2_2") (pintype "passive"))
      (node (ref "C83") (pin "2") (pinfunction "2_2") (pintype "passive"))
      (node (ref "C84") (pin "2") (pinfunction "2_2") (pintype "passive"))
      (node (ref "C85") (pin "2") (pinfunction "2_2") (pintype "passive"))
      (node (ref "C86") (pin "2") (pinfunction "2_2") (pintype "passive"))
      (node (ref "C87") (pin "2") (pinfunction "2_2") (pintype "passive"))
      (node (ref "C88") (pin "2") (pinfunction "2_2") (pintype "passive"))
      (node (ref "C89") (pin "2") (pinfunction "2_2") (pintype "passive"))
      (node (ref "C9") (pin "1") (pinfunction "1_1") (pintype "passive"))
      (node (ref "C90") (pin "2") (pinfunction "2_2") (pintype "passive"))
      (node (ref "C91") (pin "2") (pinfunction "2_2") (pintype "passive"))
      (node (ref "C92") (pin "1") (pinfunction "1_1") (pintype "passive"))
      (node (ref "C93") (pin "1") (pinfunction "1_1") (pintype "passive"))
      (node (ref "C94") (pin "2") (pinfunction "2_2") (pintype "passive"))
      (node (ref "C95") (pin "1") (pinfunction "1_1") (pintype "passive"))
      (node (ref "C96") (pin "1") (pinfunction "1_1") (pintype "passive"))
      (node (ref "D2") (pin "1") (pinfunction "C_1") (pintype "passive"))
      (node (ref "D9") (pin "C") (pinfunction "C_C") (pintype "passive"))
      (node (ref "IC10") (pin "3") (pinfunction "IN+_3") (pintype "input"))
      (node (ref "IC6") (pin "2") (pinfunction "IN-_2") (pintype "input"))
      (node (ref "JP1") (pin "2") (pinfunction "2_2") (pintype "passive"))
      (node (ref "JP2") (pin "2") (pinfunction "2_2") (pintype "passive"))
      (node (ref "JP3") (pin "2") (pinfunction "2_2") (pintype "passive"))
      (node (ref "JP4") (pin "1") (pinfunction "1_1") (pintype "passive"))
      (node (ref "R1") (pin "E") (pinfunction "3_E") (pintype "passive"))
      (node (ref "R16") (pin "1") (pinfunction "1_1") (pintype "passive"))
      (node (ref "R17") (pin "1") (pinfunction "1_1") (pintype "passive"))
      (node (ref "R18") (pin "2") (pinfunction "2_2") (pintype "passive"))
      (node (ref "R24") (pin "1") (pinfunction "1_1") (pintype "passive"))
      (node (ref "R31") (pin "1") (pinfunction "1_1") (pintype "passive"))
      (node (ref "R32") (pin "1") (pinfunction "1_1") (pintype "passive"))
      (node (ref "R39") (pin "1") (pinfunction "1_1") (pintype "passive"))
      (node (ref "R4") (pin "2") (pinfunction "2_2") (pintype "passive"))
      (node (ref "R5") (pin "2") (pinfunction "2_2") (pintype "passive"))
      (node (ref "R53") (pin "A") (pinfunction "1_A") (pintype "passive"))
      (node (ref "R9") (pin "A") (pinfunction "1_A") (pintype "passive"))
      (node (ref "S2") (pin "1") (pinfunction "1_1") (pintype "bidirectional"))
      (node (ref "S3") (pin "3") (pinfunction "3_3") (pintype "passive"))
      (node (ref "TP2") (pin "P$1") (pinfunction "P$1_P$1") (pintype "bidirectional"))
      (node (ref "X1") (pin "2") (pinfunction "2_2") (pintype "passive"))
      (node (ref "X5") (pin "2") (pinfunction "S_2") (pintype "passive"))
      (node (ref "X7") (pin "2") (pinfunction "S_2") (pintype "passive"))
    )
    (net (code "6") (name "Net-(C5-Pad1)") (class "Default")
      (node (ref "C5") (pin "1") (pinfunction "1_1") (pintype "passive"))
      (node (ref "D5") (pin "A") (pinfunction "A_A") (pintype "passive"))
      (node (ref "D6") (pin "C") (pinfunction "C_C") (pintype "passive"))
      (node (ref "R62") (pin "1") (pinfunction "1_1") (pintype "passive"))
      (node (ref "R64") (pin "2") (pinfunction "2_2") (pintype "passive"))
    )
    (net (code "7") (name "Net-(C6-Pad1)") (class "Default")
      (node (ref "C6") (pin "1") (pinfunction "1_1") (pintype "passive"))
      (node (ref "D7") (pin "A") (pinfunction "A_A") (pintype "passive"))
      (node (ref "D8") (pin "C") (pinfunction "C_C") (pintype "passive"))
      (node (ref "R63") (pin "1") (pinfunction "1_1") (pintype "passive"))
      (node (ref "R65") (pin "2") (pinfunction "2_2") (pintype "passive"))
    )
    (net (code "8") (name "Net-(C22-Pad1)") (class "Default")
      (node (ref "C22") (pin "1") (pinfunction "1_1") (pintype "passive"))
      (node (ref "S2") (pin "2") (pinfunction "2_2") (pintype "bidirectional"))
    )
    (net (code "9") (name "Net-(C71-Pad1)") (class "Default")
      (node (ref "C71") (pin "1") (pinfunction "1_1") (pintype "passive"))
      (node (ref "S2") (pin "3") (pinfunction "3_3") (pintype "bidirectional"))
    )
    (net (code "10") (name "Net-(C72-Pad1)") (class "Default")
      (node (ref "C72") (pin "1") (pinfunction "1_1") (pintype "passive"))
      (node (ref "S1") (pin "2") (pinfunction "2_2") (pintype "bidirectional"))
    )
    (net (code "11") (name "Net-(C73-Pad1)") (class "Default")
      (node (ref "C73") (pin "1") (pinfunction "1_1") (pintype "passive"))
      (node (ref "S1") (pin "3") (pinfunction "3_3") (pintype "bidirectional"))
    )
    (net (code "12") (name "Net-(C74-Pad1)") (class "Default")
      (node (ref "C74") (pin "1") (pinfunction "1_1") (pintype "passive"))
      (node (ref "S1") (pin "4") (pinfunction "4_4") (pintype "bidirectional"))
    )
    (net (code "13") (name "Net-(C75-Pad1)") (class "Default")
      (node (ref "C75") (pin "1") (pinfunction "1_1") (pintype "passive"))
      (node (ref "S1") (pin "5") (pinfunction "5_5") (pintype "bidirectional"))
    )
    (net (code "14") (name "Net-(C76-Pad1)") (class "Default")
      (node (ref "C76") (pin "1") (pinfunction "1_1") (pintype "passive"))
      (node (ref "S1") (pin "6") (pinfunction "6_6") (pintype "bidirectional"))
    )
    (net (code "15") (name "Net-(C77-Pad1)") (class "Default")
      (node (ref "C77") (pin "1") (pinfunction "1_1") (pintype "passive"))
      (node (ref "S1") (pin "7") (pinfunction "7_7") (pintype "bidirectional"))
    )
    (net (code "16") (name "Net-(C78-Pad1)") (class "Default")
      (node (ref "C78") (pin "1") (pinfunction "1_1") (pintype "passive"))
      (node (ref "S1") (pin "8") (pinfunction "8_8") (pintype "bidirectional"))
    )
    (net (code "17") (name "Net-(C79-Pad1)") (class "Default")
      (node (ref "C79") (pin "1") (pinfunction "1_1") (pintype "passive"))
      (node (ref "S1") (pin "9") (pinfunction "9_9") (pintype "bidirectional"))
    )
    (net (code "18") (name "Net-(C80-Pad1)") (class "Default")
      (node (ref "C80") (pin "1") (pinfunction "1_1") (pintype "passive"))
      (node (ref "S1") (pin "10") (pinfunction "10_10") (pintype "bidirectional"))
    )
    (net (code "19") (name "Net-(C81-Pad1)") (class "Default")
      (node (ref "C81") (pin "1") (pinfunction "1_1") (pintype "passive"))
      (node (ref "S1") (pin "11") (pinfunction "11_11") (pintype "bidirectional"))
    )
    (net (code "20") (name "Net-(C82-Pad1)") (class "Default")
      (node (ref "C82") (pin "1") (pinfunction "1_1") (pintype "passive"))
      (node (ref "S1") (pin "12") (pinfunction "12_12") (pintype "bidirectional"))
    )
    (net (code "21") (name "Net-(C83-Pad1)") (class "Default")
      (node (ref "C83") (pin "1") (pinfunction "1_1") (pintype "passive"))
      (node (ref "S2") (pin "4") (pinfunction "4_4") (pintype "bidirectional"))
    )
    (net (code "22") (name "Net-(C84-Pad1)") (class "Default")
      (node (ref "C84") (pin "1") (pinfunction "1_1") (pintype "passive"))
      (node (ref "S2") (pin "5") (pinfunction "5_5") (pintype "bidirectional"))
    )
    (net (code "23") (name "Net-(C85-Pad1)") (class "Default")
      (node (ref "C85") (pin "1") (pinfunction "1_1") (pintype "passive"))
      (node (ref "S2") (pin "6") (pinfunction "6_6") (pintype "bidirectional"))
    )
    (net (code "24") (name "Net-(C86-Pad1)") (class "Default")
      (node (ref "C86") (pin "1") (pinfunction "1_1") (pintype "passive"))
      (node (ref "S2") (pin "7") (pinfunction "7_7") (pintype "bidirectional"))
    )
    (net (code "25") (name "Net-(C87-Pad1)") (class "Default")
      (node (ref "C87") (pin "1") (pinfunction "1_1") (pintype "passive"))
      (node (ref "S2") (pin "8") (pinfunction "8_8") (pintype "bidirectional"))
    )
    (net (code "26") (name "Net-(C88-Pad1)") (class "Default")
      (node (ref "C88") (pin "1") (pinfunction "1_1") (pintype "passive"))
      (node (ref "S2") (pin "9") (pinfunction "9_9") (pintype "bidirectional"))
    )
    (net (code "27") (name "Net-(C89-Pad1)") (class "Default")
      (node (ref "C89") (pin "1") (pinfunction "1_1") (pintype "passive"))
      (node (ref "S2") (pin "10") (pinfunction "10_10") (pintype "bidirectional"))
    )
    (net (code "28") (name "Net-(C90-Pad1)") (class "Default")
      (node (ref "C90") (pin "1") (pinfunction "1_1") (pintype "passive"))
      (node (ref "S2") (pin "11") (pinfunction "11_11") (pintype "bidirectional"))
    )
    (net (code "29") (name "Net-(C91-Pad1)") (class "Default")
      (node (ref "C91") (pin "1") (pinfunction "1_1") (pintype "passive"))
      (node (ref "S2") (pin "12") (pinfunction "12_12") (pintype "bidirectional"))
    )
    (net (code "30") (name "Net-(D1-PadA)") (class "Default")
      (node (ref "D1") (pin "A") (pinfunction "A_A") (pintype "passive"))
      (node (ref "R2") (pin "1") (pinfunction "1_1") (pintype "passive"))
      (node (ref "R3") (pin "2") (pinfunction "2_2") (pintype "passive"))
    )
    (net (code "31") (name "Net-(D1-PadC)") (class "Default")
      (node (ref "D1") (pin "C") (pinfunction "C_C") (pintype "passive"))
      (node (ref "D4") (pin "A") (pinfunction "A_A") (pintype "passive"))
      (node (ref "R2") (pin "2") (pinfunction "2_2") (pintype "passive"))
      (node (ref "S3") (pin "2") (pinfunction "2_2") (pintype "passive"))
    )
    (net (code "32") (name "Net-(D2-A)") (class "Default")
      (node (ref "C1") (pin "2") (pinfunction "2_2") (pintype "passive"))
      (node (ref "D2") (pin "2") (pinfunction "A_2") (pintype "passive"))
      (node (ref "R53") (pin "E") (pinfunction "3_E") (pintype "passive"))
      (node (ref "R7") (pin "2") (pinfunction "2_2") (pintype "passive"))
      (node (ref "R9") (pin "E") (pinfunction "3_E") (pintype "passive"))
    )
    (net (code "33") (name "Net-(D4-PadC)") (class "Default")
      (node (ref "D4") (pin "C") (pinfunction "C_C") (pintype "passive"))
      (node (ref "R60") (pin "2") (pinfunction "2_2") (pintype "passive"))
    )
    (net (code "34") (name "Net-(D9-PadA)") (class "Default")
      (node (ref "D9") (pin "A") (pinfunction "A_A") (pintype "passive"))
      (node (ref "R66") (pin "1") (pinfunction "1_1") (pintype "passive"))
    )
    (net (code "35") (name "Net-(D12-1)") (class "Default")
      (node (ref "D12") (pin "A") (pinfunction "1_A") (pintype "passive"))
      (node (ref "R58") (pin "1") (pinfunction "1_1") (pintype "passive"))
      (node (ref "X4") (pin "2") (pinfunction "2_2") (pintype "passive"))
      (node (ref "X4") (pin "3") (pinfunction "2_3") (pintype "passive"))
      (node (ref "X4") (pin "4") (pinfunction "2_4") (pintype "passive"))
      (node (ref "X4") (pin "5") (pinfunction "2_5") (pintype "passive"))
    )
    (net (code "36") (name "Net-(D12-2)") (class "Default")
      (node (ref "C6") (pin "2") (pinfunction "2_2") (pintype "passive"))
      (node (ref "D12") (pin "C") (pinfunction "2_C") (pintype "passive"))
      (node (ref "R65") (pin "1") (pinfunction "1_1") (pintype "passive"))
      (node (ref "X4") (pin "1") (pinfunction "1_1") (pintype "passive"))
    )
    (net (code "37") (name "Net-(D13-1)") (class "Default")
      (node (ref "D13") (pin "A") (pinfunction "1_A") (pintype "passive"))
      (node (ref "R6") (pin "1") (pinfunction "1_1") (pintype "passive"))
      (node (ref "X2") (pin "2") (pinfunction "2_2") (pintype "passive"))
      (node (ref "X2") (pin "3") (pinfunction "2_3") (pintype "passive"))
      (node (ref "X2") (pin "4") (pinfunction "2_4") (pintype "passive"))
      (node (ref "X2") (pin "5") (pinfunction "2_5") (pintype "passive"))
    )
    (net (code "38") (name "Net-(D13-2)") (class "Default")
      (node (ref "C5") (pin "2") (pinfunction "2_2") (pintype "passive"))
      (node (ref "D13") (pin "C") (pinfunction "2_C") (pintype "passive"))
      (node (ref "R64") (pin "1") (pinfunction "1_1") (pintype "passive"))
      (node (ref "X2") (pin "1") (pinfunction "1_1") (pintype "passive"))
    )
    (net (code "39") (name "Net-(D14-PadA)") (class "Default")
      (node (ref "D14") (pin "A") (pinfunction "A_A") (pintype "passive"))
      (node (ref "R18") (pin "1") (pinfunction "1_1") (pintype "passive"))
    )
    (net (code "40") (name "Net-(IC1-IN+)") (class "Default")
      (node (ref "IC1") (pin "3") (pinfunction "IN+_3") (pintype "input"))
      (node (ref "R20") (pin "1") (pinfunction "1_1") (pintype "passive"))
      (node (ref "R24") (pin "2") (pinfunction "2_2") (pintype "passive"))
    )
    (net (code "41") (name "Net-(IC1-IN-)") (class "Default")
      (node (ref "IC1") (pin "2") (pinfunction "IN-_2") (pintype "input"))
      (node (ref "R19") (pin "1") (pinfunction "1_1") (pintype "passive"))
      (node (ref "R23") (pin "2") (pinfunction "2_2") (pintype "passive"))
    )
    (net (code "42") (name "Net-(IC1-OUT)") (class "Default")
      (node (ref "IC1") (pin "6") (pinfunction "OUT_6") (pintype "output"))
      (node (ref "R23") (pin "1") (pinfunction "1_1") (pintype "passive"))
      (node (ref "R25") (pin "2") (pinfunction "2_2") (pintype "passive"))
      (node (ref "R40") (pin "2") (pinfunction "2_2") (pintype "passive"))
    )
    (net (code "43") (name "Net-(IC2-COMP)") (class "Default")
      (node (ref "C13") (pin "1") (pinfunction "1_1") (pintype "passive"))
      (node (ref "IC2") (pin "8") (pinfunction "COMP_8") (pintype "passive"))
    )
    (net (code "44") (name "Net-(IC2-IN+)") (class "Default")
      (node (ref "C10") (pin "1") (pinfunction "1_1") (pintype "passive"))
      (node (ref "IC2") (pin "3") (pinfunction "IN+_3") (pintype "input"))
      (node (ref "JP4") (pin "2") (pinfunction "2_2") (pintype "passive"))
      (node (ref "R14") (pin "2") (pinfunction "2_2") (pintype "passive"))
      (node (ref "R16") (pin "2") (pinfunction "2_2") (pintype "passive"))
      (node (ref "R70") (pin "2") (pinfunction "SA_2") (pintype "passive"))
      (node (ref "X6") (pin "2") (pinfunction "S_2") (pintype "passive"))
    )
    (net (code "45") (name "Net-(IC2-IN-)") (class "Default")
      (node (ref "C14") (pin "1") (pinfunction "1_1") (pintype "passive"))
      (node (ref "IC2") (pin "2") (pinfunction "IN-_2") (pintype "input"))
      (node (ref "R13") (pin "2") (pinfunction "2_2") (pintype "passive"))
      (node (ref "R21") (pin "2") (pinfunction "2_2") (pintype "passive"))
    )
    (net (code "46") (name "Net-(IC2-OUT)") (class "Default")
      (node (ref "C13") (pin "2") (pinfunction "2_2") (pintype "passive"))
      (node (ref "C14") (pin "2") (pinfunction "2_2") (pintype "passive"))
      (node (ref "IC2") (pin "6") (pinfunction "OUT_6") (pintype "output"))
      (node (ref "R19") (pin "2") (pinfunction "2_2") (pintype "passive"))
      (node (ref "R21") (pin "1") (pinfunction "1_1") (pintype "passive"))
    )
    (net (code "47") (name "Net-(IC3-IN)") (class "Default")
      (node (ref "IC3") (pin "3") (pinfunction "IN_3") (pintype "input"))
      (node (ref "R57") (pin "1") (pinfunction "1_1") (pintype "passive"))
    )
    (net (code "48") (name "Net-(IC3-OUT)") (class "Default")
      (node (ref "IC3") (pin "6") (pinfunction "OUT_6") (pintype "output"))
      (node (ref "R63") (pin "2") (pinfunction "2_2") (pintype "passive"))
    )
    (net (code "49") (name "Net-(IC4-COMP)") (class "Default")
      (node (ref "C12") (pin "1") (pinfunction "1_1") (pintype "passive"))
      (node (ref "IC4") (pin "8") (pinfunction "COMP_8") (pintype "passive"))
    )
    (net (code "50") (name "Net-(IC4-IN+)") (class "Default")
      (node (ref "C11") (pin "1") (pinfunction "1_1") (pintype "passive"))
      (node (ref "IC4") (pin "3") (pinfunction "IN+_3") (pintype "input"))
      (node (ref "JP3") (pin "1") (pinfunction "1_1") (pintype "passive"))
      (node (ref "R15") (pin "1") (pinfunction "1_1") (pintype "passive"))
      (node (ref "R17") (pin "2") (pinfunction "2_2") (pintype "passive"))
      (node (ref "R70") (pin "3") (pinfunction "SB_3") (pintype "passive"))
      (node (ref "X6") (pin "3") (pinfunction "S_3") (pintype "passive"))
    )
    (net (code "51") (name "Net-(IC4-IN-)") (class "Default")
      (node (ref "C15") (pin "1") (pinfunction "1_1") (pintype "passive"))
      (node (ref "IC4") (pin "2") (pinfunction "IN-_2") (pintype "input"))
      (node (ref "R13") (pin "1") (pinfunction "1_1") (pintype "passive"))
      (node (ref "R22") (pin "2") (pinfunction "2_2") (pintype "passive"))
    )
    (net (code "52") (name "Net-(IC4-OUT)") (class "Default")
      (node (ref "C12") (pin "2") (pinfunction "2_2") (pintype "passive"))
      (node (ref "C15") (pin "2") (pinfunction "2_2") (pintype "passive"))
      (node (ref "IC4") (pin "6") (pinfunction "OUT_6") (pintype "output"))
      (node (ref "R20") (pin "2") (pinfunction "2_2") (pintype "passive"))
      (node (ref "R22") (pin "1") (pinfunction "1_1") (pintype "passive"))
    )
    (net (code "53") (name "Net-(IC5-IN+)") (class "Default")
      (node (ref "IC5") (pin "3") (pinfunction "IN+_3") (pintype "input"))
      (node (ref "R42") (pin "1") (pinfunction "1_1") (pintype "passive"))
    )
    (net (code "54") (name "Net-(IC5-IN-)") (class "Default")
      (node (ref "IC5") (pin "2") (pinfunction "IN-_2") (pintype "input"))
      (node (ref "R43") (pin "2") (pinfunction "2_2") (pintype "passive"))
    )
    (net (code "55") (name "Net-(IC5-OUT)") (class "Default")
      (node (ref "C72") (pin "2") (pinfunction "2_2") (pintype "passive"))
      (node (ref "C73") (pin "2") (pinfunction "2_2") (pintype "passive"))
      (node (ref "C74") (pin "2") (pinfunction "2_2") (pintype "passive"))
      (node (ref "C75") (pin "2") (pinfunction "2_2") (pintype "passive"))
      (node (ref "C76") (pin "2") (pinfunction "2_2") (pintype "passive"))
      (node (ref "C77") (pin "2") (pinfunction "2_2") (pintype "passive"))
      (node (ref "C78") (pin "2") (pinfunction "2_2") (pintype "passive"))
      (node (ref "C79") (pin "2") (pinfunction "2_2") (pintype "passive"))
      (node (ref "C80") (pin "2") (pinfunction "2_2") (pintype "passive"))
      (node (ref "C81") (pin "2") (pinfunction "2_2") (pintype "passive"))
      (node (ref "C82") (pin "2") (pinfunction "2_2") (pintype "passive"))
      (node (ref "IC5") (pin "6") (pinfunction "OUT_6") (pintype "output"))
      (node (ref "R45") (pin "2") (pinfunction "2_2") (pintype "passive"))
      (node (ref "S1") (pin "1") (pinfunction "1_1") (pintype "bidirectional"))
    )
    (net (code "56") (name "Net-(IC6-IN+)") (class "Default")
      (node (ref "IC6") (pin "3") (pinfunction "IN+_3") (pintype "input"))
      (node (ref "R25") (pin "1") (pinfunction "1_1") (pintype "passive"))
    )
    (net (code "57") (name "Net-(IC6-OUT)") (class "Default")
      (node (ref "IC6") (pin "6") (pinfunction "OUT_6") (pintype "output"))
      (node (ref "R27") (pin "2") (pinfunction "2_2") (pintype "passive"))
    )
    (net (code "58") (name "Net-(IC7-COMP)") (class "Default")
      (node (ref "C19") (pin "1") (pinfunction "1_1") (pintype "passive"))
      (node (ref "IC7") (pin "8") (pinfunction "COMP_8") (pintype "passive"))
    )
    (net (code "59") (name "Net-(IC7-IN+)") (class "Default")
      (node (ref "C16") (pin "1") (pinfunction "1_1") (pintype "passive"))
      (node (ref "IC7") (pin "3") (pinfunction "IN+_3") (pintype "input"))
      (node (ref "R29") (pin "2") (pinfunction "2_2") (pintype "passive"))
      (node (ref "R31") (pin "2") (pinfunction "2_2") (pintype "passive"))
    )
    (net (code "60") (name "Net-(IC7-IN-)") (class "Default")
      (node (ref "C20") (pin "1") (pinfunction "1_1") (pintype "passive"))
      (node (ref "IC7") (pin "2") (pinfunction "IN-_2") (pintype "input"))
      (node (ref "R28") (pin "2") (pinfunction "2_2") (pintype "passive"))
      (node (ref "R36") (pin "2") (pinfunction "2_2") (pintype "passive"))
    )
    (net (code "61") (name "Net-(IC7-OUT)") (class "Default")
      (node (ref "C19") (pin "2") (pinfunction "2_2") (pintype "passive"))
      (node (ref "C20") (pin "2") (pinfunction "2_2") (pintype "passive"))
      (node (ref "IC7") (pin "6") (pinfunction "OUT_6") (pintype "output"))
      (node (ref "R34") (pin "2") (pinfunction "2_2") (pintype "passive"))
      (node (ref "R36") (pin "1") (pinfunction "1_1") (pintype "passive"))
    )
    (net (code "62") (name "Net-(IC8-COMP)") (class "Default")
      (node (ref "C18") (pin "1") (pinfunction "1_1") (pintype "passive"))
      (node (ref "IC8") (pin "8") (pinfunction "COMP_8") (pintype "passive"))
    )
    (net (code "63") (name "Net-(IC8-IN+)") (class "Default")
      (node (ref "C17") (pin "1") (pinfunction "1_1") (pintype "passive"))
      (node (ref "IC8") (pin "3") (pinfunction "IN+_3") (pintype "input"))
      (node (ref "R30") (pin "1") (pinfunction "1_1") (pintype "passive"))
      (node (ref "R32") (pin "2") (pinfunction "2_2") (pintype "passive"))
    )
    (net (code "64") (name "Net-(IC8-IN-)") (class "Default")
      (node (ref "C21") (pin "1") (pinfunction "1_1") (pintype "passive"))
      (node (ref "IC8") (pin "2") (pinfunction "IN-_2") (pintype "input"))
      (node (ref "R28") (pin "1") (pinfunction "1_1") (pintype "passive"))
      (node (ref "R37") (pin "2") (pinfunction "2_2") (pintype "passive"))
    )
    (net (code "65") (name "Net-(IC8-OUT)") (class "Default")
      (node (ref "C18") (pin "2") (pinfunction "2_2") (pintype "passive"))
      (node (ref "C21") (pin "2") (pinfunction "2_2") (pintype "passive"))
      (node (ref "IC8") (pin "6") (pinfunction "OUT_6") (pintype "output"))
      (node (ref "R35") (pin "2") (pinfunction "2_2") (pintype "passive"))
      (node (ref "R37") (pin "1") (pinfunction "1_1") (pintype "passive"))
    )
    (net (code "66") (name "Net-(IC9-IN+)") (class "Default")
      (node (ref "IC9") (pin "3") (pinfunction "IN+_3") (pintype "input"))
      (node (ref "R35") (pin "1") (pinfunction "1_1") (pintype "passive"))
      (node (ref "R39") (pin "2") (pinfunction "2_2") (pintype "passive"))
    )
    (net (code "67") (name "Net-(IC9-IN-)") (class "Default")
      (node (ref "IC9") (pin "2") (pinfunction "IN-_2") (pintype "input"))
      (node (ref "R34") (pin "1") (pinfunction "1_1") (pintype "passive"))
      (node (ref "R38") (pin "2") (pinfunction "2_2") (pintype "passive"))
    )
    (net (code "68") (name "Net-(IC9-OUT)") (class "Default")
      (node (ref "IC9") (pin "6") (pinfunction "OUT_6") (pintype "output"))
      (node (ref "R33") (pin "2") (pinfunction "2_2") (pintype "passive"))
      (node (ref "R38") (pin "1") (pinfunction "1_1") (pintype "passive"))
      (node (ref "TP1") (pin "P$1") (pinfunction "P$1_P$1") (pintype "bidirectional"))
    )
    (net (code "69") (name "Net-(IC10-IN-)") (class "Default")
      (node (ref "IC10") (pin "2") (pinfunction "IN-_2") (pintype "input"))
      (node (ref "R33") (pin "1") (pinfunction "1_1") (pintype "passive"))
      (node (ref "R40") (pin "1") (pinfunction "1_1") (pintype "passive"))
      (node (ref "R41") (pin "2") (pinfunction "2_2") (pintype "passive"))
    )
    (net (code "70") (name "Net-(IC10-OUT)") (class "Default")
      (node (ref "IC10") (pin "6") (pinfunction "OUT_6") (pintype "output"))
      (node (ref "R0") (pin "2") (pinfunction "2_2") (pintype "passive"))
      (node (ref "R0") (pin "3") (pinfunction "3_3") (pintype "passive"))
      (node (ref "R42") (pin "2") (pinfunction "2_2") (pintype "passive"))
    )
    (net (code "71") (name "Net-(IC11-IN+)") (class "Default")
      (node (ref "IC11") (pin "3") (pinfunction "IN+_3") (pintype "input"))
      (node (ref "R45") (pin "1") (pinfunction "1_1") (pintype "passive"))
      (node (ref "R46") (pin "1") (pinfunction "1_1") (pintype "passive"))
    )
    (net (code "72") (name "Net-(IC11-IN-)") (class "Default")
      (node (ref "IC11") (pin "2") (pinfunction "IN-_2") (pintype "input"))
      (node (ref "R47") (pin "2") (pinfunction "2_2") (pintype "passive"))
    )
    (net (code "73") (name "Net-(IC11-OUT)") (class "Default")
      (node (ref "IC11") (pin "6") (pinfunction "OUT_6") (pintype "output"))
      (node (ref "R48") (pin "1") (pinfunction "1_1") (pintype "passive"))
      (node (ref "R50") (pin "A") (pinfunction "1_A") (pintype "passive"))
      (node (ref "R50") (pin "S") (pinfunction "2_S") (pintype "passive"))
    )
    (net (code "74") (name "Net-(IC12-IN+)") (class "Default")
      (node (ref "C23") (pin "1") (pinfunction "1_1") (pintype "passive"))
      (node (ref "IC12") (pin "3") (pinfunction "IN+_3") (pintype "input"))
      (node (ref "R52") (pin "1") (pinfunction "1_1") (pintype "passive"))
    )
    (net (code "75") (name "Net-(IC12-IN-)") (class "Default")
      (node (ref "IC12") (pin "2") (pinfunction "IN-_2") (pintype "input"))
      (node (ref "IC12") (pin "6") (pinfunction "OUT_6") (pintype "output"))
      (node (ref "S3") (pin "1") (pinfunction "1_1") (pintype "passive"))
    )
    (net (code "76") (name "Net-(IC13-IN+)") (class "Default")
      (node (ref "IC13") (pin "3") (pinfunction "IN+_3") (pintype "input"))
      (node (ref "R4") (pin "1") (pinfunction "1_1") (pintype "passive"))
      (node (ref "R5") (pin "1") (pinfunction "1_1") (pintype "passive"))
      (node (ref "R6") (pin "2") (pinfunction "2_2") (pintype "passive"))
    )
    (net (code "77") (name "Net-(IC13-IN-)") (class "Default")
      (node (ref "IC13") (pin "2") (pinfunction "IN-_2") (pintype "input"))
      (node (ref "R3") (pin "1") (pinfunction "1_1") (pintype "passive"))
      (node (ref "R55") (pin "1") (pinfunction "1_1") (pintype "passive"))
      (node (ref "R8") (pin "2") (pinfunction "2_2") (pintype "passive"))
    )
    (net (code "78") (name "Net-(IC13-OUT)") (class "Default")
      (node (ref "IC13") (pin "6") (pinfunction "OUT_6") (pintype "output"))
      (node (ref "R61") (pin "2") (pinfunction "2_2") (pintype "passive"))
      (node (ref "R8") (pin "1") (pinfunction "1_1") (pintype "passive"))
    )
    (net (code "79") (name "Net-(IC14-IN+)") (class "Default")
      (node (ref "C2") (pin "2") (pinfunction "2_2") (pintype "passive"))
      (node (ref "IC14") (pin "3") (pinfunction "IN+_3") (pintype "input"))
      (node (ref "R9") (pin "S") (pinfunction "2_S") (pintype "passive"))
    )
    (net (code "80") (name "Net-(IC15-IN+)") (class "Default")
      (node (ref "C4") (pin "2") (pinfunction "2_2") (pintype "passive"))
      (node (ref "IC15") (pin "3") (pinfunction "IN+_3") (pintype "input"))
      (node (ref "R53") (pin "S") (pinfunction "2_S") (pintype "passive"))
    )
    (net (code "81") (name "Net-(IC16-IN+)") (class "Default")
      (node (ref "IC16") (pin "3") (pinfunction "IN+_3") (pintype "input"))
      (node (ref "R58") (pin "2") (pinfunction "2_2") (pintype "passive"))
      (node (ref "R60") (pin "1") (pinfunction "1_1") (pintype "passive"))
    )
    (net (code "82") (name "Net-(IC16-IN-)") (class "Default")
      (node (ref "IC16") (pin "2") (pinfunction "IN-_2") (pintype "input"))
      (node (ref "R56") (pin "1") (pinfunction "1_1") (pintype "passive"))
      (node (ref "R59") (pin "2") (pinfunction "2_2") (pintype "passive"))
    )
    (net (code "83") (name "Net-(IC16-OUT)") (class "Default")
      (node (ref "IC16") (pin "6") (pinfunction "OUT_6") (pintype "output"))
      (node (ref "R57") (pin "2") (pinfunction "2_2") (pintype "passive"))
      (node (ref "R59") (pin "1") (pinfunction "1_1") (pintype "passive"))
    )
    (net (code "84") (name "Net-(IC17-IN)") (class "Default")
      (node (ref "IC17") (pin "3") (pinfunction "IN_3") (pintype "input"))
      (node (ref "R61") (pin "1") (pinfunction "1_1") (pintype "passive"))
    )
    (net (code "85") (name "Net-(IC17-OUT)") (class "Default")
      (node (ref "IC17") (pin "6") (pinfunction "OUT_6") (pintype "output"))
      (node (ref "R62") (pin "2") (pinfunction "2_2") (pintype "passive"))
    )
    (net (code "86") (name "Net-(JP1-Pad1)") (class "Default")
      (node (ref "JP1") (pin "1") (pinfunction "1_1") (pintype "passive"))
      (node (ref "R10") (pin "1") (pinfunction "1_1") (pintype "passive"))
      (node (ref "R55") (pin "2") (pinfunction "2_2") (pintype "passive"))
    )
    (net (code "87") (name "Net-(JP2-Pad1)") (class "Default")
      (node (ref "JP2") (pin "1") (pinfunction "1_1") (pintype "passive"))
      (node (ref "R54") (pin "1") (pinfunction "1_1") (pintype "passive"))
      (node (ref "R56") (pin "2") (pinfunction "2_2") (pintype "passive"))
    )
    (net (code "88") (name "Net-(R0-Pad1)") (class "Default")
      (node (ref "R0") (pin "1") (pinfunction "1_1") (pintype "passive"))
      (node (ref "R41") (pin "1") (pinfunction "1_1") (pintype "passive"))
    )
    (net (code "89") (name "Net-(R1-1)") (class "Default")
      (node (ref "R1") (pin "A") (pinfunction "1_A") (pintype "passive"))
      (node (ref "R1") (pin "S") (pinfunction "2_S") (pintype "passive"))
      (node (ref "R44") (pin "1") (pinfunction "1_1") (pintype "passive"))
    )
    (net (code "90") (name "Net-(R27-Pad1)") (class "Default")
      (node (ref "R27") (pin "1") (pinfunction "1_1") (pintype "passive"))
      (node (ref "X1") (pin "1") (pinfunction "1_1") (pintype "passive"))
    )
    (net (code "91") (name "Net-(R29-Pad1)") (class "Default")
      (node (ref "R29") (pin "1") (pinfunction "1_1") (pintype "passive"))
      (node (ref "X3") (pin "1") (pinfunction "1_1") (pintype "passive"))
    )
    (net (code "92") (name "Net-(R30-Pad2)") (class "Default")
      (node (ref "R30") (pin "2") (pinfunction "2_2") (pintype "passive"))
      (node (ref "X3") (pin "2") (pinfunction "2_2") (pintype "passive"))
    )
    (net (code "93") (name "Net-(R43-Pad1)") (class "Default")
      (node (ref "R43") (pin "1") (pinfunction "1_1") (pintype "passive"))
      (node (ref "R44") (pin "2") (pinfunction "2_2") (pintype "passive"))
      (node (ref "S1") (pin "13") (pinfunction "13_13") (pintype "bidirectional"))
    )
    (net (code "94") (name "Net-(R47-Pad1)") (class "Default")
      (node (ref "R47") (pin "1") (pinfunction "1_1") (pintype "passive"))
      (node (ref "R48") (pin "2") (pinfunction "2_2") (pintype "passive"))
      (node (ref "R49") (pin "2") (pinfunction "2_2") (pintype "passive"))
    )
    (net (code "95") (name "Net-(R50-3)") (class "Default")
      (node (ref "R50") (pin "E") (pinfunction "3_E") (pintype "passive"))
      (node (ref "R52") (pin "2") (pinfunction "2_2") (pintype "passive"))
    )
    (net (code "96") (name "Net-(R51-1)") (class "Default")
      (node (ref "R49") (pin "1") (pinfunction "1_1") (pintype "passive"))
      (node (ref "R51") (pin "A") (pinfunction "1_A") (pintype "passive"))
      (node (ref "R51") (pin "S") (pinfunction "2_S") (pintype "passive"))
    )
    (net (code "97") (name "Net-(R51-3)") (class "Default")
      (node (ref "R51") (pin "E") (pinfunction "3_E") (pintype "passive"))
      (node (ref "S2") (pin "13") (pinfunction "13_13") (pintype "bidirectional"))
    )
    (net (code "98") (name "Net-(R70-A)") (class "Default")
      (node (ref "R14") (pin "1") (pinfunction "1_1") (pintype "passive"))
      (node (ref "R70") (pin "1") (pinfunction "A_1") (pintype "passive"))
    )
    (net (code "99") (name "Net-(R70-B)") (class "Default")
      (node (ref "R15") (pin "2") (pinfunction "2_2") (pintype "passive"))
      (node (ref "R70") (pin "4") (pinfunction "B_4") (pintype "passive"))
    )
    (net (code "100") (name "unconnected-(IC2-OFF-Pad1)") (class "Default")
      (node (ref "IC2") (pin "1") (pinfunction "OFF_1") (pintype "passive"))
    )
    (net (code "101") (name "unconnected-(IC2-OFF-Pad5)") (class "Default")
      (node (ref "IC2") (pin "5") (pinfunction "OFF_5") (pintype "passive"))
    )
    (net (code "102") (name "unconnected-(IC3-BW-Pad1)") (class "Default")
      (node (ref "IC3") (pin "1") (pinfunction "BW_1") (pintype "passive"))
    )
    (net (code "103") (name "unconnected-(IC4-OFF-Pad1)") (class "Default")
      (node (ref "IC4") (pin "1") (pinfunction "OFF_1") (pintype "passive"))
    )
    (net (code "104") (name "unconnected-(IC4-OFF-Pad5)") (class "Default")
      (node (ref "IC4") (pin "5") (pinfunction "OFF_5") (pintype "passive"))
    )
    (net (code "105") (name "unconnected-(IC7-OFF-Pad1)") (class "Default")
      (node (ref "IC7") (pin "1") (pinfunction "OFF_1") (pintype "passive"))
    )
    (net (code "106") (name "unconnected-(IC7-OFF-Pad5)") (class "Default")
      (node (ref "IC7") (pin "5") (pinfunction "OFF_5") (pintype "passive"))
    )
    (net (code "107") (name "unconnected-(IC8-OFF-Pad1)") (class "Default")
      (node (ref "IC8") (pin "1") (pinfunction "OFF_1") (pintype "passive"))
    )
    (net (code "108") (name "unconnected-(IC8-OFF-Pad5)") (class "Default")
      (node (ref "IC8") (pin "5") (pinfunction "OFF_5") (pintype "passive"))
    )
    (net (code "109") (name "unconnected-(IC17-BW-Pad1)") (class "Default")
      (node (ref "IC17") (pin "1") (pinfunction "BW_1") (pintype "passive"))
    )
  )
)
